# EVB-NORA-B2_SCHEM_0004_Connectors_Memory.net
KiCad netlist of a schematic drawn in Altium Designer
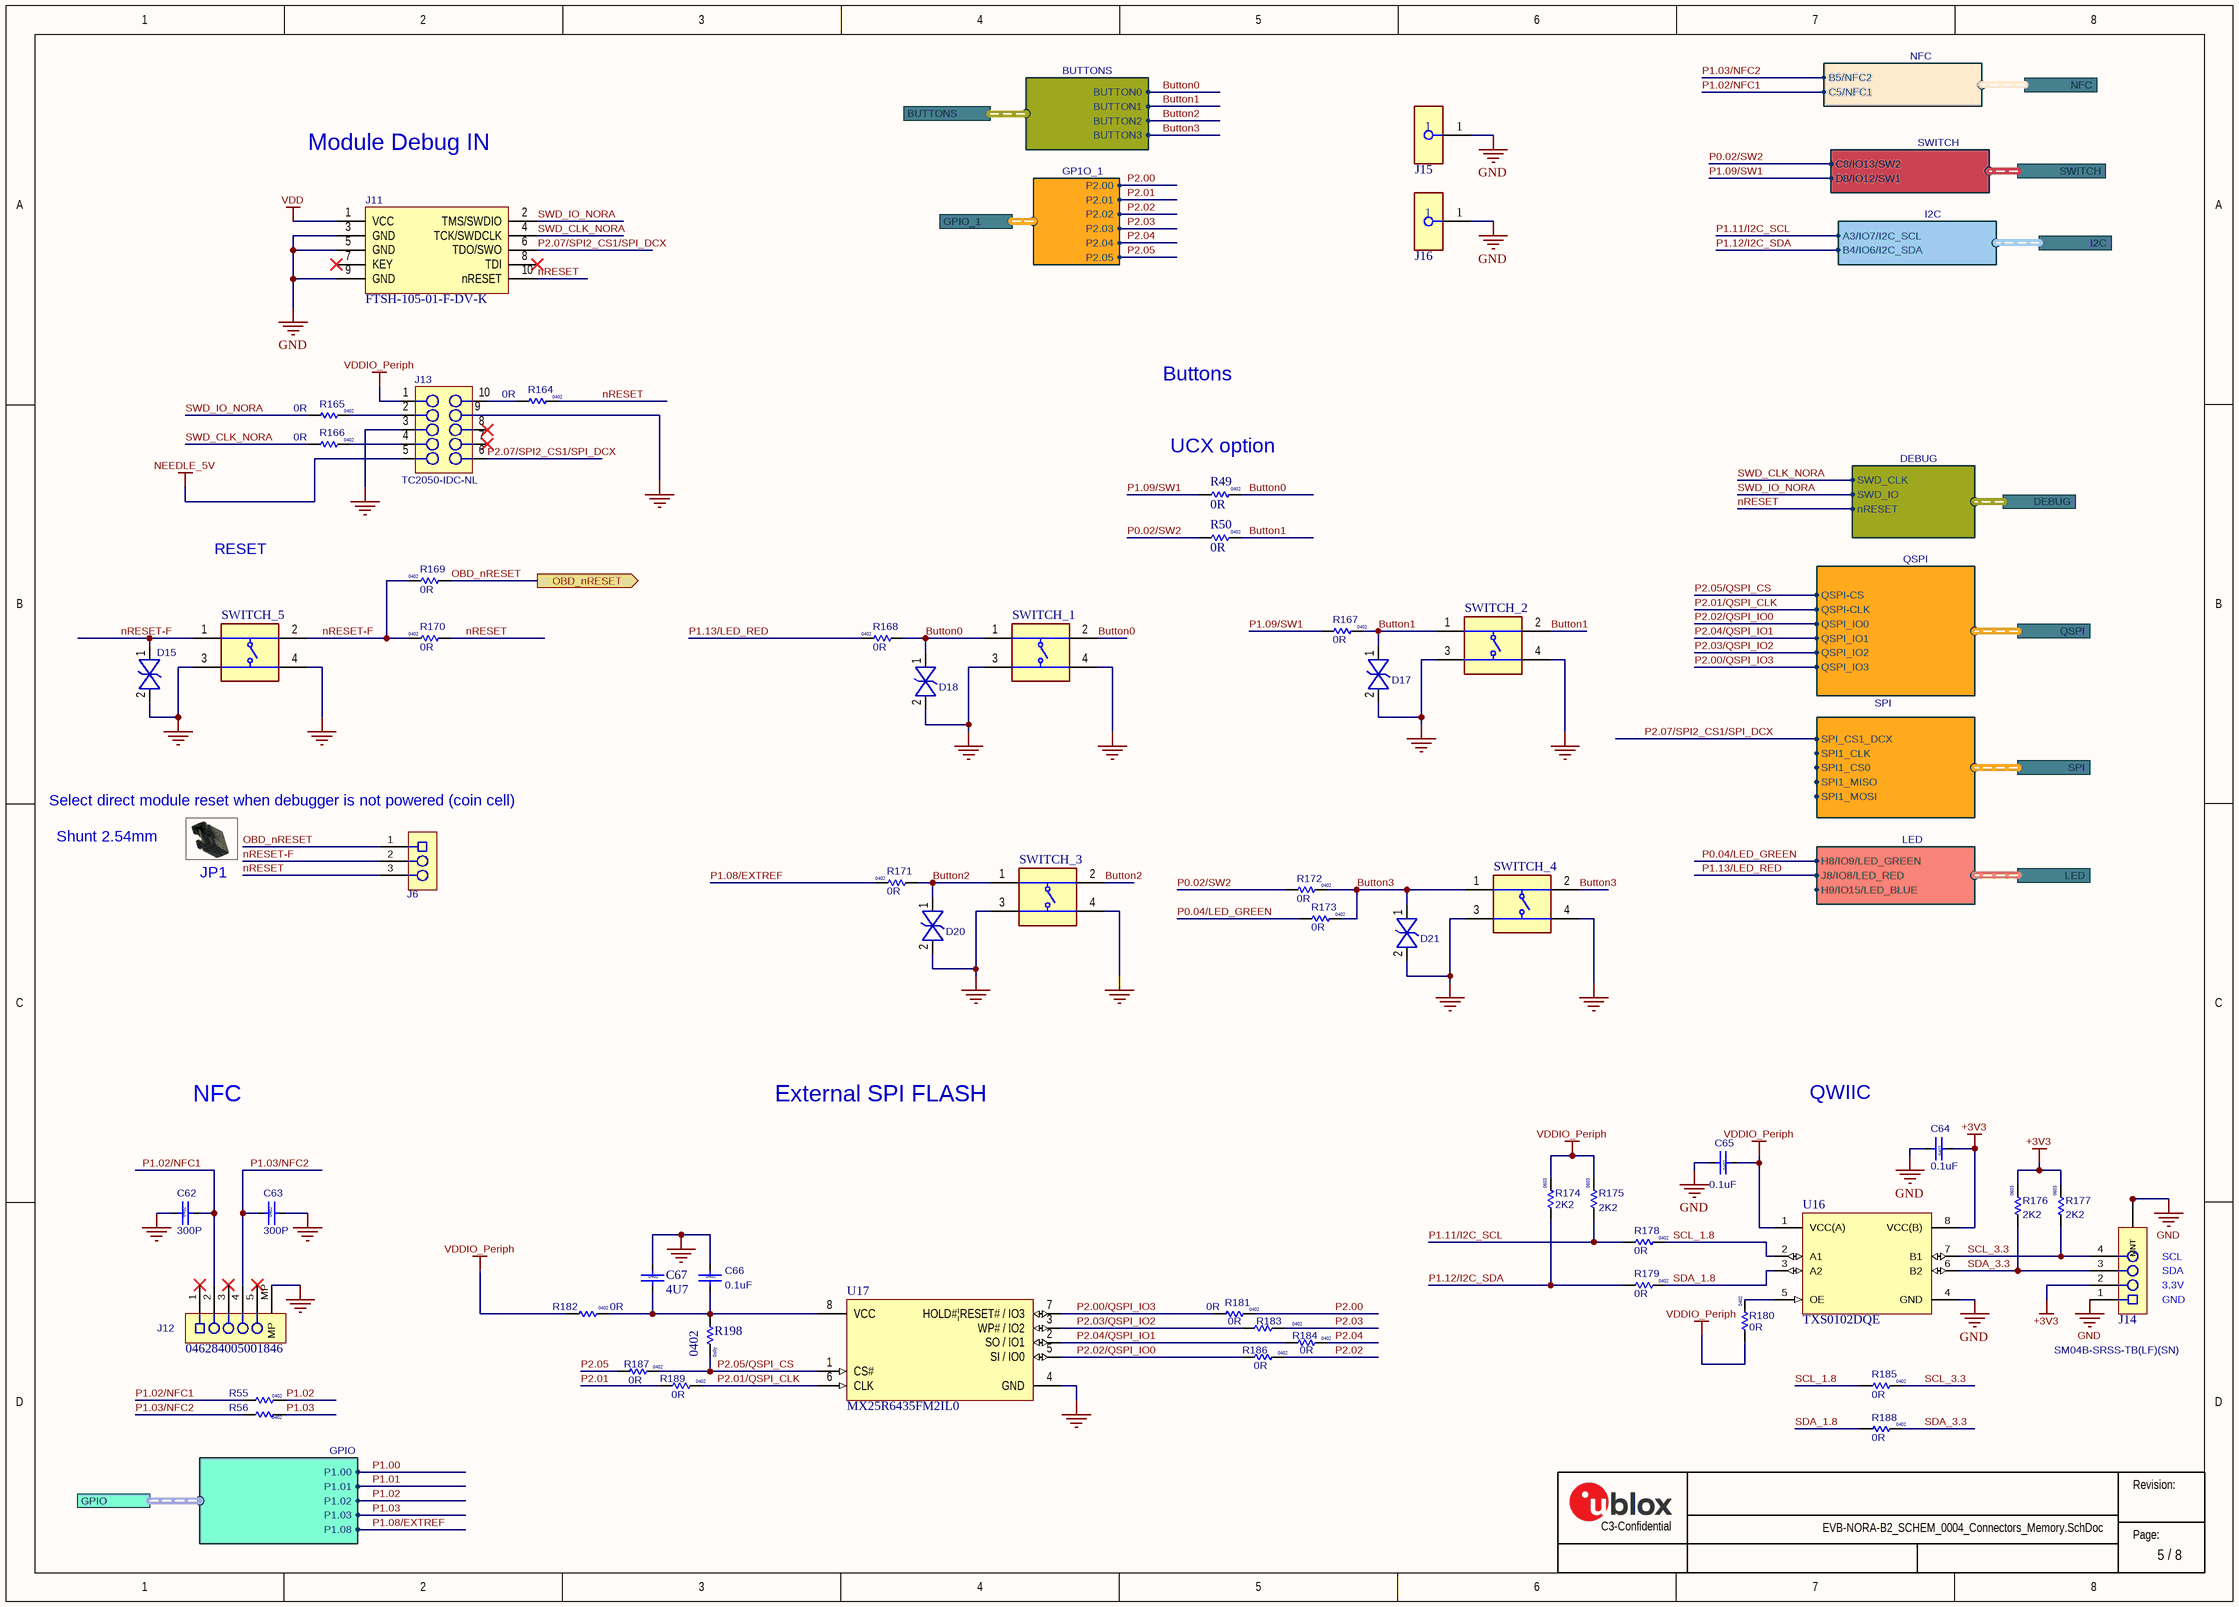
[diagram p0: EVB-NORA-B2_SCHEM_0004_Connectors_Memory.SchDoc]

(export (version "E")
  (design (tool "Eeschema 10.0.6"))
  (components
    (comp (ref "C62")
      (value "300P")
      (footprint "Cap 0402 HD")
      (description "CAP CER C0G 0402 300P 50V")
      (fields
        (field (name "SIZE") "0402")
        (field (name "PART NUMBER") "UBXH01-0000594")
        (field (name "MANUFACTURER") "Murata Manufacturing Company, Ltd.")
        (field (name "EDITOR") "eric.moog")
      )
      (libsource (lib "UBX_Parts_DB_Lib") (part "Cap Chip"))
    )
    (comp (ref "C63")
      (value "300P")
      (footprint "Cap 0402 HD")
      (description "CAP CER C0G 0402 300P 50V")
      (fields
        (field (name "SIZE") "0402")
        (field (name "PART NUMBER") "UBXH01-0000594")
        (field (name "MANUFACTURER") "Murata Manufacturing Company, Ltd.")
        (field (name "EDITOR") "eric.moog")
      )
      (libsource (lib "UBX_Parts_DB_Lib") (part "Cap Chip"))
    )
    (comp (ref "C64")
      (value "0.1uF")
      (footprint "Cap 0402 HD")
      (description "Cap, Ceramic 0.1uF 10V 10% X5R 0402")
      (fields
        (field (name "SIZE") "0402")
        (field (name "PART NUMBER") "120-00016")
        (field (name "MANUFACTURER") "Murata Electronics North America")
      )
      (libsource (lib "Arena_Parts_DB_Lib") (part "Cap Chip"))
    )
    (comp (ref "C65")
      (value "0.1uF")
      (footprint "Cap 0402 HD")
      (description "Cap, Ceramic 0.1uF 10V 10% X5R 0402")
      (fields
        (field (name "SIZE") "0402")
        (field (name "PART NUMBER") "120-00016")
        (field (name "MANUFACTURER") "Murata Electronics North America")
      )
      (libsource (lib "Arena_Parts_DB_Lib") (part "Cap Chip"))
    )
    (comp (ref "C66")
      (value "0.1uF")
      (footprint "Cap 0402 HD")
      (description "Cap, Ceramic 0.1uF 10V 10% X5R 0402")
      (fields
        (field (name "SIZE") "0402")
        (field (name "PART NUMBER") "120-00016")
        (field (name "MANUFACTURER") "Murata Electronics North America")
      )
      (libsource (lib "Arena_Parts_DB_Lib") (part "Cap Chip"))
    )
    (comp (ref "C67")
      (value "4U7")
      (footprint "Cap 0402 HD")
      (description "CAP CER X5R 0402 4U7 20% 10V")
      (fields
        (field (name "SIZE") "0402")
        (field (name "PART NUMBER") "UBXH01-0000243")
        (field (name "TOLERANCE") "20%")
        (field (name "EDITOR") "martin.pilik")
        (field (name "RELEASED BY") "fabrice.bret-dibat")
      )
      (libsource (lib "UBX_Parts_DB_Lib") (part "Cap Chip"))
    )
    (comp (ref "D15")
      (value "110-00019")
      (footprint "SOD-923")
      (description "ESD9B3.3ST5G")
      (fields (field (name "MANUFACTURER") "ON Semiconductor") (field (name "VOLTAGE") "3.3V"))
      (libsource (lib "Arena_Parts_DB_Lib") (part "Diode_TVS"))
    )
    (comp (ref "D17")
      (value "110-00019")
      (footprint "SOD-923")
      (description "ESD9B3.3ST5G")
      (fields (field (name "MANUFACTURER") "ON Semiconductor") (field (name "VOLTAGE") "3.3V"))
      (libsource (lib "Arena_Parts_DB_Lib") (part "Diode_TVS"))
    )
    (comp (ref "D18")
      (value "110-00019")
      (footprint "SOD-923")
      (description "ESD9B3.3ST5G")
      (fields (field (name "MANUFACTURER") "ON Semiconductor") (field (name "VOLTAGE") "3.3V"))
      (libsource (lib "Arena_Parts_DB_Lib") (part "Diode_TVS"))
    )
    (comp (ref "D20")
      (value "110-00019")
      (footprint "SOD-923")
      (description "ESD9B3.3ST5G")
      (fields (field (name "MANUFACTURER") "ON Semiconductor") (field (name "VOLTAGE") "3.3V"))
      (libsource (lib "Arena_Parts_DB_Lib") (part "Diode_TVS"))
    )
    (comp (ref "D21")
      (value "110-00019")
      (footprint "SOD-923")
      (description "ESD9B3.3ST5G")
      (fields (field (name "MANUFACTURER") "ON Semiconductor") (field (name "VOLTAGE") "3.3V"))
      (libsource (lib "Arena_Parts_DB_Lib") (part "Diode_TVS"))
    )
    (comp (ref "J6")
      (value "UBXH04-0000792")
      (footprint "HDR-0.1P-3Pin-1Row-SMT")
      (description "1-ROW SMD CONN 100MIL GRID 3 -PIN 100V 3A")
      (fields (field (name "MANUFACTURER") "HARWiN") (field (name "EDITOR") "eric.moog"))
      (libsource (lib "UBX_Parts_DB_Lib") (part "CON-3Pin_1Row"))
    )
    (comp (ref "J11")
      (value "130-00099")
      (footprint "HDR.050P-10Pin-2x5-SMT_Key")
      (description "Header 0.05\" 10Pin 2Row SMD Black")
      (fields (field (name "MANUFACTURER") "Samtec") (field (name "MANUFACTURER P/N") "FTSH-105-01-F-DV-K"))
      (libsource (lib "Arena_Parts_DB_Lib") (part "JTAG-10Pin"))
    )
    (comp (ref "J12")
      (value "UBXH04-0000798")
      (footprint "AVX/Kyocera - 046284005001846")
      (description "0.50MM PITCH SMD RA FFC FPC CONN 5 -PIN 50V 400mA")
      (fields
        (field (name "MANUFACTURER P/N") "046284005001846")
        (field (name "VOLTAGE") "50V")
        (field (name "MANUFACTURER") "AVX")
        (field (name "EDITOR") "eric.moog")
      )
      (libsource (lib "UBX_Parts_DB_Lib") (part "CON-5Pin_1Row-046284005001846"))
    )
    (comp (ref "J13")
      (value "TC2050-IDC-NL")
      (footprint "TC2050-IDC-NL")
      (description "CON PADS FOR CBL PLUG-OF-NAILS 10-PIN NO LEGS")
      (fields
        (field (name "MANUFACTURER P/N") "TC2050-IDC-NL")
        (field (name "MANUFACTURER") "TAG Connect")
        (field (name "ADDED BY") "Paul B")
      )
      (libsource (lib "LEGACY_Rigado_AltiumLib") (part "CON-10Pin_2Row_ALT"))
    )
    (comp (ref "J14")
      (value "UBXH04-0000797")
      (footprint "SM04B-SRSS-TB")
      (description "CONN JST SH SERIES SMT 4 POS MALE 1MM RA 50V 1A")
      (fields
        (field (name "MANUFACTURER PART NUMBER 1") "SM04B-SRSS-TB(LF)(SN)")
        (field (name "VOLTAGE") "None")
        (field (name "MANUFACTURER") "JST")
        (field (name "EDITOR") "eric.moog")
      )
      (libsource (lib "UBX_Parts_DB_Lib") (part "SM04B-SRSS-TB"))
    )
    (comp (ref "J15")
      (value "~")
      (footprint "Harwin_0_MFG")
      (libsource (lib "Conn_Harwin_S1751-46R_eec") (part "S1751-46R"))
    )
    (comp (ref "J16")
      (value "~")
      (footprint "Harwin_0_MFG")
      (libsource (lib "Conn_Harwin_S1751-46R_eec") (part "S1751-46R"))
    )
    (comp (ref "R49")
      (value "0R")
      (footprint "RES_0402_1100Lx600Wx400H_500x600Pad_400G_FLX")
      (description "RES THICK FILM CHIP 0402 0R 0 100mW")
      (fields
        (field (name "SIZE") "0402")
        (field (name "PART NUMBER") "UBXH18-0003002")
        (field (name "TOLERANCE") "0")
        (field (name "EDITOR") "charlotte.biber")
        (field (name "RELEASED BY") "peter.mueller")
      )
      (libsource (lib "UBX_Parts_DB_Lib") (part "Res sm"))
    )
    (comp (ref "R50")
      (value "0R")
      (footprint "RES_0402_1100Lx600Wx400H_500x600Pad_400G_FLX")
      (description "RES THICK FILM CHIP 0402 0R 0 100mW")
      (fields
        (field (name "SIZE") "0402")
        (field (name "PART NUMBER") "UBXH18-0003002")
        (field (name "TOLERANCE") "0")
        (field (name "EDITOR") "charlotte.biber")
        (field (name "RELEASED BY") "peter.mueller")
      )
      (libsource (lib "UBX_Parts_DB_Lib") (part "Res sm"))
    )
    (comp (ref "R55")
      (value "UBXH18-0003002")
      (footprint "RES 0402 HD")
      (description "RES THICK FILM CHIP 0402 0R 0 100mW")
      (fields
        (field (name "SIZE") "0402")
        (field (name "TOLERANCE") "0")
        (field (name "MANUFACTURER") "KOA")
        (field (name "EDITOR") "charlotte.biber")
        (field (name "RELEASED BY") "peter.mueller")
      )
      (libsource (lib "UBX_Parts_DB_Lib") (part "Res sm"))
    )
    (comp (ref "R56")
      (value "UBXH18-0003002")
      (footprint "RES 0402 HD")
      (description "RES THICK FILM CHIP 0402 0R 0 100mW")
      (fields
        (field (name "SIZE") "0402")
        (field (name "TOLERANCE") "0")
        (field (name "MANUFACTURER") "KOA")
        (field (name "EDITOR") "charlotte.biber")
        (field (name "RELEASED BY") "peter.mueller")
      )
      (libsource (lib "UBX_Parts_DB_Lib") (part "Res sm"))
    )
    (comp (ref "R164")
      (value "0R")
      (footprint "RES 0402 HD")
      (description "RES THICK FILM CHIP 0402 0R 0 100mW")
      (fields
        (field (name "SIZE") "0402")
        (field (name "PART NUMBER") "UBXH18-0003002")
        (field (name "TOLERANCE") "0")
        (field (name "EDITOR") "charlotte.biber")
        (field (name "RELEASED BY") "peter.mueller")
      )
      (libsource (lib "UBX_Parts_DB_Lib") (part "Res sm"))
    )
    (comp (ref "R165")
      (value "0R")
      (footprint "RES 0402 HD")
      (description "RES THICK FILM CHIP 0402 0R 0 100mW")
      (fields
        (field (name "SIZE") "0402")
        (field (name "PART NUMBER") "UBXH18-0003002")
        (field (name "TOLERANCE") "0")
        (field (name "EDITOR") "charlotte.biber")
        (field (name "RELEASED BY") "peter.mueller")
      )
      (libsource (lib "UBX_Parts_DB_Lib") (part "Res sm"))
    )
    (comp (ref "R166")
      (value "0R")
      (footprint "RES 0402 HD")
      (description "RES THICK FILM CHIP 0402 0R 0 100mW")
      (fields
        (field (name "SIZE") "0402")
        (field (name "PART NUMBER") "UBXH18-0003002")
        (field (name "TOLERANCE") "0")
        (field (name "EDITOR") "charlotte.biber")
        (field (name "RELEASED BY") "peter.mueller")
      )
      (libsource (lib "UBX_Parts_DB_Lib") (part "Res sm"))
    )
    (comp (ref "R167")
      (value "0R")
      (footprint "RES 0402 HD")
      (description "RES THICK FILM CHIP 0402 0R 0 100mW")
      (fields
        (field (name "SIZE") "0402")
        (field (name "PART NUMBER") "UBXH18-0003002")
        (field (name "TOLERANCE") "0")
        (field (name "EDITOR") "charlotte.biber")
        (field (name "RELEASED BY") "peter.mueller")
      )
      (libsource (lib "UBX_Parts_DB_Lib") (part "Res sm"))
    )
    (comp (ref "R168")
      (value "0R")
      (footprint "RES 0402 HD")
      (description "RES THICK FILM CHIP 0402 0R 0 100mW")
      (fields
        (field (name "SIZE") "0402")
        (field (name "PART NUMBER") "UBXH18-0003002")
        (field (name "TOLERANCE") "0")
        (field (name "EDITOR") "charlotte.biber")
        (field (name "RELEASED BY") "peter.mueller")
      )
      (libsource (lib "UBX_Parts_DB_Lib") (part "Res sm"))
    )
    (comp (ref "R169")
      (value "0R")
      (footprint "RES 0402 HD")
      (description "RES THICK FILM CHIP 0402 0R 0 100mW")
      (fields
        (field (name "SIZE") "0402")
        (field (name "PART NUMBER") "UBXH18-0003002")
        (field (name "TOLERANCE") "0")
        (field (name "EDITOR") "charlotte.biber")
        (field (name "RELEASED BY") "peter.mueller")
      )
      (libsource (lib "UBX_Parts_DB_Lib") (part "Res sm"))
    )
    (comp (ref "R170")
      (value "0R")
      (footprint "RES 0402 HD")
      (description "RES THICK FILM CHIP 0402 0R 0 100mW")
      (fields
        (field (name "SIZE") "0402")
        (field (name "PART NUMBER") "UBXH18-0003002")
        (field (name "TOLERANCE") "0")
        (field (name "EDITOR") "charlotte.biber")
        (field (name "RELEASED BY") "peter.mueller")
      )
      (libsource (lib "UBX_Parts_DB_Lib") (part "Res sm"))
    )
    (comp (ref "R171")
      (value "0R")
      (footprint "RES 0402 HD")
      (description "RES THICK FILM CHIP 0402 0R 0 100mW")
      (fields
        (field (name "SIZE") "0402")
        (field (name "PART NUMBER") "UBXH18-0003002")
        (field (name "TOLERANCE") "0")
        (field (name "EDITOR") "charlotte.biber")
        (field (name "RELEASED BY") "peter.mueller")
      )
      (libsource (lib "UBX_Parts_DB_Lib") (part "Res sm"))
    )
    (comp (ref "R172")
      (value "0R")
      (footprint "RES 0402 HD")
      (description "RES THICK FILM CHIP 0402 0R 0 100mW")
      (fields
        (field (name "SIZE") "0402")
        (field (name "PART NUMBER") "UBXH18-0003002")
        (field (name "TOLERANCE") "0")
        (field (name "EDITOR") "charlotte.biber")
        (field (name "RELEASED BY") "peter.mueller")
      )
      (libsource (lib "UBX_Parts_DB_Lib") (part "Res sm"))
    )
    (comp (ref "R173")
      (value "0R")
      (footprint "RES 0402 HD")
      (description "RES THICK FILM CHIP 0402 0R 0 100mW")
      (fields
        (field (name "SIZE") "0402")
        (field (name "PART NUMBER") "UBXH18-0003002")
        (field (name "TOLERANCE") "0")
        (field (name "EDITOR") "charlotte.biber")
        (field (name "RELEASED BY") "peter.mueller")
      )
      (libsource (lib "UBX_Parts_DB_Lib") (part "Res sm"))
    )
    (comp (ref "R174")
      (value "2K2")
      (footprint "RES_0603_1700Lx950Wx600H_600x1000Pad_800G_FLX")
      (description "RES THICK FILM CHIP 0603 2K2 5% 100mW")
      (fields
        (field (name "SIZE") "0603")
        (field (name "PART NUMBER") "UBXH18-0007081")
        (field (name "TOLERANCE") "5%")
        (field (name "EDITOR") "roland.rust")
        (field (name "RELEASED BY") "roland.rust")
      )
      (libsource (lib "UBX_Parts_DB_Lib") (part "Res sm"))
    )
    (comp (ref "R175")
      (value "2K2")
      (footprint "RES_0603_1700Lx950Wx600H_600x1000Pad_800G_FLX")
      (description "RES THICK FILM CHIP 0603 2K2 5% 100mW")
      (fields
        (field (name "SIZE") "0603")
        (field (name "PART NUMBER") "UBXH18-0007081")
        (field (name "TOLERANCE") "5%")
        (field (name "EDITOR") "roland.rust")
        (field (name "RELEASED BY") "roland.rust")
      )
      (libsource (lib "UBX_Parts_DB_Lib") (part "Res sm"))
    )
    (comp (ref "R176")
      (value "2K2")
      (footprint "RES_0603_1700Lx950Wx600H_600x1000Pad_800G_FLX")
      (description "RES THICK FILM CHIP 0603 2K2 5% 100mW")
      (fields
        (field (name "SIZE") "0603")
        (field (name "PART NUMBER") "UBXH18-0007081")
        (field (name "TOLERANCE") "5%")
        (field (name "EDITOR") "roland.rust")
        (field (name "RELEASED BY") "roland.rust")
      )
      (libsource (lib "UBX_Parts_DB_Lib") (part "Res sm"))
    )
    (comp (ref "R177")
      (value "2K2")
      (footprint "RES_0603_1700Lx950Wx600H_600x1000Pad_800G_FLX")
      (description "RES THICK FILM CHIP 0603 2K2 5% 100mW")
      (fields
        (field (name "SIZE") "0603")
        (field (name "PART NUMBER") "UBXH18-0007081")
        (field (name "TOLERANCE") "5%")
        (field (name "EDITOR") "roland.rust")
        (field (name "RELEASED BY") "roland.rust")
      )
      (libsource (lib "UBX_Parts_DB_Lib") (part "Res sm"))
    )
    (comp (ref "R178")
      (value "0R")
      (footprint "RES 0402 HD")
      (description "RES THICK FILM CHIP 0402 0R 0 100mW")
      (fields
        (field (name "SIZE") "0402")
        (field (name "PART NUMBER") "UBXH18-0003002")
        (field (name "TOLERANCE") "0")
        (field (name "EDITOR") "charlotte.biber")
        (field (name "RELEASED BY") "peter.mueller")
      )
      (libsource (lib "UBX_Parts_DB_Lib") (part "Res sm"))
    )
    (comp (ref "R179")
      (value "0R")
      (footprint "RES 0402 HD")
      (description "RES THICK FILM CHIP 0402 0R 0 100mW")
      (fields
        (field (name "SIZE") "0402")
        (field (name "PART NUMBER") "UBXH18-0003002")
        (field (name "TOLERANCE") "0")
        (field (name "EDITOR") "charlotte.biber")
        (field (name "RELEASED BY") "peter.mueller")
      )
      (libsource (lib "UBX_Parts_DB_Lib") (part "Res sm"))
    )
    (comp (ref "R180")
      (value "0R")
      (footprint "RES 0402 HD")
      (description "RES THICK FILM CHIP 0402 0R 0 100mW")
      (fields
        (field (name "SIZE") "0402")
        (field (name "PART NUMBER") "UBXH18-0003002")
        (field (name "TOLERANCE") "0")
        (field (name "EDITOR") "charlotte.biber")
        (field (name "RELEASED BY") "peter.mueller")
      )
      (libsource (lib "UBX_Parts_DB_Lib") (part "Res sm"))
    )
    (comp (ref "R181")
      (value "0R")
      (footprint "RES 0402 HD")
      (description "RES THICK FILM CHIP 0402 0R 0 100mW")
      (fields
        (field (name "SIZE") "0402")
        (field (name "PART NUMBER") "UBXH18-0003002")
        (field (name "TOLERANCE") "0")
        (field (name "EDITOR") "charlotte.biber")
        (field (name "RELEASED BY") "peter.mueller")
      )
      (libsource (lib "UBX_Parts_DB_Lib") (part "Res sm"))
    )
    (comp (ref "R182")
      (value "0R")
      (footprint "RES 0402 HD")
      (description "RES THICK FILM CHIP 0402 0R 0 100mW")
      (fields
        (field (name "SIZE") "0402")
        (field (name "PART NUMBER") "UBXH18-0003002")
        (field (name "TOLERANCE") "0")
        (field (name "EDITOR") "charlotte.biber")
        (field (name "RELEASED BY") "peter.mueller")
      )
      (libsource (lib "UBX_Parts_DB_Lib") (part "Res sm"))
    )
    (comp (ref "R183")
      (value "0R")
      (footprint "RES 0402 HD")
      (description "RES THICK FILM CHIP 0402 0R 0 100mW")
      (fields
        (field (name "SIZE") "0402")
        (field (name "PART NUMBER") "UBXH18-0003002")
        (field (name "TOLERANCE") "0")
        (field (name "EDITOR") "charlotte.biber")
        (field (name "RELEASED BY") "peter.mueller")
      )
      (libsource (lib "UBX_Parts_DB_Lib") (part "Res sm"))
    )
    (comp (ref "R184")
      (value "0R")
      (footprint "RES 0402 HD")
      (description "RES THICK FILM CHIP 0402 0R 0 100mW")
      (fields
        (field (name "SIZE") "0402")
        (field (name "PART NUMBER") "UBXH18-0003002")
        (field (name "TOLERANCE") "0")
        (field (name "EDITOR") "charlotte.biber")
        (field (name "RELEASED BY") "peter.mueller")
      )
      (libsource (lib "UBX_Parts_DB_Lib") (part "Res sm"))
    )
    (comp (ref "R185")
      (value "0R")
      (footprint "RES 0402 HD")
      (description "RES THICK FILM CHIP 0402 0R 0 100mW")
      (fields
        (field (name "SIZE") "0402")
        (field (name "PART NUMBER") "UBXH18-0003002")
        (field (name "TOLERANCE") "0")
        (field (name "EDITOR") "charlotte.biber")
        (field (name "RELEASED BY") "peter.mueller")
      )
      (libsource (lib "UBX_Parts_DB_Lib") (part "Res sm"))
    )
    (comp (ref "R186")
      (value "0R")
      (footprint "RES 0402 HD")
      (description "RES THICK FILM CHIP 0402 0R 0 100mW")
      (fields
        (field (name "SIZE") "0402")
        (field (name "PART NUMBER") "UBXH18-0003002")
        (field (name "TOLERANCE") "0")
        (field (name "EDITOR") "charlotte.biber")
        (field (name "RELEASED BY") "peter.mueller")
      )
      (libsource (lib "UBX_Parts_DB_Lib") (part "Res sm"))
    )
    (comp (ref "R187")
      (value "0R")
      (footprint "RES 0402 HD")
      (description "RES THICK FILM CHIP 0402 0R 0 100mW")
      (fields
        (field (name "SIZE") "0402")
        (field (name "PART NUMBER") "UBXH18-0003002")
        (field (name "TOLERANCE") "0")
        (field (name "EDITOR") "charlotte.biber")
        (field (name "RELEASED BY") "peter.mueller")
      )
      (libsource (lib "UBX_Parts_DB_Lib") (part "Res sm"))
    )
    (comp (ref "R188")
      (value "0R")
      (footprint "RES 0402 HD")
      (description "RES THICK FILM CHIP 0402 0R 0 100mW")
      (fields
        (field (name "SIZE") "0402")
        (field (name "PART NUMBER") "UBXH18-0003002")
        (field (name "TOLERANCE") "0")
        (field (name "EDITOR") "charlotte.biber")
        (field (name "RELEASED BY") "peter.mueller")
      )
      (libsource (lib "UBX_Parts_DB_Lib") (part "Res sm"))
    )
    (comp (ref "R189")
      (value "0R")
      (footprint "RES 0402 HD")
      (description "RES THICK FILM CHIP 0402 0R 0 100mW")
      (fields
        (field (name "SIZE") "0402")
        (field (name "PART NUMBER") "UBXH18-0003002")
        (field (name "TOLERANCE") "0")
        (field (name "EDITOR") "charlotte.biber")
        (field (name "RELEASED BY") "peter.mueller")
      )
      (libsource (lib "UBX_Parts_DB_Lib") (part "Res sm"))
    )
    (comp (ref "R198")
      (value "UBXH18-0000005")
      (footprint "RES 0402 HD")
      (description "RES THICK FILM CHIP 0402 100K 1% 63mW")
      (fields
        (field (name "SIZE") "0402")
        (field (name "TOLERANCE") "1%")
        (field (name "MANUFACTURER") "KOA")
        (field (name "CASE/PACKAGE") "0x0y")
        (field (name "EDITOR") "dario.antonaz")
        (field (name "RELEASED BY") "sandro.sestan")
      )
      (libsource (lib "UBX_Parts_DB_Lib") (part "Res sm"))
    )
    (comp (ref "SWITCH_1")
      (value "~")
      (footprint "PTS810SJG250SMTRLFS")
      (description "Switch")
      (fields
        (field (name "MANUFACTURER_PART_NUMBER") "PTS810SJK250SMTRLFS")
        (field (name "MOUSER PART NUMBER") "611-PTS810SJK250SMTR")
      )
      (libsource (lib "SamacSys") (part "PTS810SJK250SMTRLFS"))
    )
    (comp (ref "SWITCH_2")
      (value "~")
      (footprint "PTS810SJG250SMTRLFS")
      (description "Switch")
      (fields
        (field (name "MANUFACTURER_PART_NUMBER") "PTS810SJK250SMTRLFS")
        (field (name "MOUSER PART NUMBER") "611-PTS810SJK250SMTR")
      )
      (libsource (lib "SamacSys") (part "PTS810SJK250SMTRLFS"))
    )
    (comp (ref "SWITCH_3")
      (value "~")
      (footprint "PTS810SJG250SMTRLFS")
      (description "Switch")
      (fields
        (field (name "MANUFACTURER_PART_NUMBER") "PTS810SJK250SMTRLFS")
        (field (name "MOUSER PART NUMBER") "611-PTS810SJK250SMTR")
      )
      (libsource (lib "SamacSys") (part "PTS810SJK250SMTRLFS"))
    )
    (comp (ref "SWITCH_4")
      (value "~")
      (footprint "PTS810SJG250SMTRLFS")
      (description "Switch")
      (fields
        (field (name "MANUFACTURER_PART_NUMBER") "PTS810SJK250SMTRLFS")
        (field (name "MOUSER PART NUMBER") "611-PTS810SJK250SMTR")
      )
      (libsource (lib "SamacSys") (part "PTS810SJK250SMTRLFS"))
    )
    (comp (ref "SWITCH_5")
      (value "~")
      (footprint "PTS810SJG250SMTRLFS")
      (description "Switch")
      (fields
        (field (name "MANUFACTURER_PART_NUMBER") "PTS810SJK250SMTRLFS")
        (field (name "MOUSER PART NUMBER") "611-PTS810SJK250SMTR")
      )
      (libsource (lib "SamacSys") (part "PTS810SJK250SMTRLFS"))
    )
    (comp (ref "U16")
      (value "TXS0102DQE")
      (footprint "DQE0008A")
      (description "TXS0102 2-BIT BIDIRECTIONAL VOLTAGE-LEVEL TRANSLATOR X2SON-8 TXS0102DQE 5.5V")
      (fields
        (field (name "PART NUMBER") "UBXH10-0000108")
        (field (name "MANUFACTURER") "Texas Instruments")
        (field (name "EDITOR") "eric.moog")
      )
      (libsource (lib "UBX_Parts_DB_Lib") (part "TXS0102DQE"))
    )
    (comp (ref "U17")
      (value "UBXH13-0000149")
      (footprint "SOIC-8")
      (description "MACRONIX MX25R6435FM2IL0 64MBIT SERIAL QUAD I/O SPI FLASH MEMORY 1.65 - 3.6V 8-SOP (200mil)")
      (fields (field (name "MANUFACTURER P/N") "MX25R6435FM2IL0") (field (name "OWNER") "Hozaifa Abdelgadir"))
      (libsource (lib "UBX_Arena") (part "SPI_Flash_Memory_8Pin"))
    )
  )
  (nets
    (net (code "11") (name "+3V3") (class "Default")
      (node (ref "C64") (pin "1") (pinfunction "1_1") (pintype "passive"))
      (node (ref "J14") (pin "2") (pinfunction "2_2") (pintype "passive"))
      (node (ref "R176") (pin "2") (pinfunction "2_2") (pintype "passive"))
      (node (ref "R177") (pin "2") (pinfunction "2_2") (pintype "passive"))
      (node (ref "U16") (pin "8") (pinfunction "VCC(B)_8") (pintype "power_in"))
    )
    (net (code "12") (name "/Button0") (class "Default")
      (node (ref "D18") (pin "1") (pintype "passive"))
      (node (ref "R168") (pin "1") (pinfunction "1_1") (pintype "passive"))
      (node (ref "R49") (pin "2") (pinfunction "2_2") (pintype "passive"))
      (node (ref "SWITCH_1") (pin "1") (pinfunction "1_1") (pintype "passive"))
      (node (ref "SWITCH_1") (pin "2") (pinfunction "2_2") (pintype "passive"))
    )
    (net (code "13") (name "/Button1") (class "Default")
      (node (ref "D17") (pin "1") (pintype "passive"))
      (node (ref "R167") (pin "1") (pinfunction "1_1") (pintype "passive"))
      (node (ref "R50") (pin "2") (pinfunction "2_2") (pintype "passive"))
      (node (ref "SWITCH_2") (pin "1") (pinfunction "1_1") (pintype "passive"))
      (node (ref "SWITCH_2") (pin "2") (pinfunction "2_2") (pintype "passive"))
    )
    (net (code "14") (name "/Button2") (class "Default")
      (node (ref "D20") (pin "1") (pintype "passive"))
      (node (ref "R171") (pin "1") (pinfunction "1_1") (pintype "passive"))
      (node (ref "SWITCH_3") (pin "1") (pinfunction "1_1") (pintype "passive"))
      (node (ref "SWITCH_3") (pin "2") (pinfunction "2_2") (pintype "passive"))
    )
    (net (code "15") (name "/Button3") (class "Default")
      (node (ref "D21") (pin "1") (pintype "passive"))
      (node (ref "R172") (pin "1") (pinfunction "1_1") (pintype "passive"))
      (node (ref "R173") (pin "1") (pinfunction "1_1") (pintype "passive"))
      (node (ref "SWITCH_4") (pin "1") (pinfunction "1_1") (pintype "passive"))
      (node (ref "SWITCH_4") (pin "2") (pinfunction "2_2") (pintype "passive"))
    )
    (net (code "16") (name "/OBD_nRESET") (class "Default")
      (node (ref "J6") (pin "1") (pinfunction "1_1") (pintype "passive"))
      (node (ref "R169") (pin "1") (pinfunction "1_1") (pintype "passive"))
    )
    (net (code "17") (name "/P0.02{slash}SW2") (class "Default")
      (node (ref "R172") (pin "2") (pinfunction "2_2") (pintype "passive"))
      (node (ref "R50") (pin "1") (pinfunction "1_1") (pintype "passive"))
    )
    (net (code "18") (name "/P0.04{slash}LED_GREEN") (class "Default")
      (node (ref "R173") (pin "2") (pinfunction "2_2") (pintype "passive"))
    )
    (net (code "21") (name "/P1.02") (class "Default")
      (node (ref "R55") (pin "1") (pinfunction "1_1") (pintype "passive"))
    )
    (net (code "22") (name "/P1.02{slash}NFC1") (class "Default")
      (node (ref "C62") (pin "2") (pinfunction "2_2") (pintype "passive"))
      (node (ref "J12") (pin "2") (pinfunction "2_2") (pintype "passive"))
      (node (ref "R55") (pin "2") (pinfunction "2_2") (pintype "passive"))
    )
    (net (code "23") (name "/P1.03") (class "Default")
      (node (ref "R56") (pin "1") (pinfunction "1_1") (pintype "passive"))
    )
    (net (code "24") (name "/P1.03{slash}NFC2") (class "Default")
      (node (ref "C63") (pin "1") (pinfunction "1_1") (pintype "passive"))
      (node (ref "J12") (pin "4") (pinfunction "4_4") (pintype "passive"))
      (node (ref "R56") (pin "2") (pinfunction "2_2") (pintype "passive"))
    )
    (net (code "25") (name "/P1.08{slash}EXTREF") (class "Default")
      (node (ref "R171") (pin "2") (pinfunction "2_2") (pintype "passive"))
    )
    (net (code "26") (name "/P1.09{slash}SW1") (class "Default")
      (node (ref "R167") (pin "2") (pinfunction "2_2") (pintype "passive"))
      (node (ref "R49") (pin "1") (pinfunction "1_1") (pintype "passive"))
    )
    (net (code "27") (name "/P1.11{slash}I2C_SCL") (class "Default")
      (node (ref "R175") (pin "1") (pinfunction "1_1") (pintype "passive"))
      (node (ref "R178") (pin "2") (pinfunction "2_2") (pintype "passive"))
    )
    (net (code "28") (name "/P1.12{slash}I2C_SDA") (class "Default")
      (node (ref "R174") (pin "1") (pinfunction "1_1") (pintype "passive"))
      (node (ref "R179") (pin "2") (pinfunction "2_2") (pintype "passive"))
    )
    (net (code "29") (name "/P1.13{slash}LED_RED") (class "Default")
      (node (ref "R168") (pin "2") (pinfunction "2_2") (pintype "passive"))
    )
    (net (code "30") (name "/P2.00") (class "Default")
      (node (ref "R181") (pin "1") (pinfunction "1_1") (pintype "passive"))
    )
    (net (code "31") (name "/P2.00{slash}QSPI_IO3") (class "Default")
      (node (ref "R181") (pin "2") (pinfunction "2_2") (pintype "passive"))
      (node (ref "U17") (pin "7") (pinfunction "HOLD#¦RESET#_/_IO3_7") (pintype "bidirectional"))
    )
    (net (code "32") (name "/P2.01") (class "Default")
      (node (ref "R189") (pin "2") (pinfunction "2_2") (pintype "passive"))
    )
    (net (code "33") (name "/P2.01{slash}QSPI_CLK") (class "Default")
      (node (ref "R189") (pin "1") (pinfunction "1_1") (pintype "passive"))
      (node (ref "U17") (pin "6") (pinfunction "CLK_6") (pintype "input"))
    )
    (net (code "34") (name "/P2.02") (class "Default")
      (node (ref "R186") (pin "1") (pinfunction "1_1") (pintype "passive"))
    )
    (net (code "35") (name "/P2.02{slash}QSPI_IO0") (class "Default")
      (node (ref "R186") (pin "2") (pinfunction "2_2") (pintype "passive"))
      (node (ref "U17") (pin "5") (pinfunction "SI_/_IO0_5") (pintype "bidirectional"))
    )
    (net (code "36") (name "/P2.03") (class "Default")
      (node (ref "R183") (pin "1") (pinfunction "1_1") (pintype "passive"))
    )
    (net (code "37") (name "/P2.03{slash}QSPI_IO2") (class "Default")
      (node (ref "R183") (pin "2") (pinfunction "2_2") (pintype "passive"))
      (node (ref "U17") (pin "3") (pinfunction "WP#_/_IO2_3") (pintype "bidirectional"))
    )
    (net (code "38") (name "/P2.04") (class "Default")
      (node (ref "R184") (pin "1") (pinfunction "1_1") (pintype "passive"))
    )
    (net (code "39") (name "/P2.04{slash}QSPI_IO1") (class "Default")
      (node (ref "R184") (pin "2") (pinfunction "2_2") (pintype "passive"))
      (node (ref "U17") (pin "2") (pinfunction "SO_/_IO1_2") (pintype "bidirectional"))
    )
    (net (code "40") (name "/P2.05") (class "Default")
      (node (ref "R187") (pin "2") (pinfunction "2_2") (pintype "passive"))
    )
    (net (code "41") (name "/P2.05{slash}QSPI_CS") (class "Default")
      (node (ref "R187") (pin "1") (pinfunction "1_1") (pintype "passive"))
      (node (ref "R198") (pin "2") (pinfunction "2_2") (pintype "passive"))
      (node (ref "U17") (pin "1") (pinfunction "CS#_1") (pintype "input"))
    )
    (net (code "42") (name "/P2.07{slash}SPI2_CS1{slash}SPI_DCX") (class "Default")
      (node (ref "J11") (pin "6") (pinfunction "TDO/SWO_6") (pintype "passive"))
      (node (ref "J13") (pin "6") (pintype "passive"))
    )
    (net (code "43") (name "/SCL_1.8") (class "Default")
      (node (ref "R178") (pin "1") (pinfunction "1_1") (pintype "passive"))
      (node (ref "R185") (pin "2") (pinfunction "2_2") (pintype "passive"))
      (node (ref "U16") (pin "2") (pinfunction "A1_2") (pintype "bidirectional"))
    )
    (net (code "44") (name "/SCL_3.3") (class "Default")
      (node (ref "J14") (pin "4") (pinfunction "4_4") (pintype "passive"))
      (node (ref "R177") (pin "1") (pinfunction "1_1") (pintype "passive"))
      (node (ref "R185") (pin "1") (pinfunction "1_1") (pintype "passive"))
      (node (ref "U16") (pin "7") (pinfunction "B1_7") (pintype "bidirectional"))
    )
    (net (code "45") (name "/SDA_1.8") (class "Default")
      (node (ref "R179") (pin "1") (pinfunction "1_1") (pintype "passive"))
      (node (ref "R188") (pin "2") (pinfunction "2_2") (pintype "passive"))
      (node (ref "U16") (pin "3") (pinfunction "A2_3") (pintype "bidirectional"))
    )
    (net (code "46") (name "/SDA_3.3") (class "Default")
      (node (ref "J14") (pin "3") (pinfunction "3_3") (pintype "passive"))
      (node (ref "R176") (pin "1") (pinfunction "1_1") (pintype "passive"))
      (node (ref "R188") (pin "1") (pinfunction "1_1") (pintype "passive"))
      (node (ref "U16") (pin "6") (pinfunction "B2_6") (pintype "bidirectional"))
    )
    (net (code "47") (name "/SWD_CLK_NORA") (class "Default")
      (node (ref "J11") (pin "4") (pinfunction "TCK/SWDCLK_4") (pintype "passive"))
      (node (ref "R166") (pin "2") (pinfunction "2_2") (pintype "passive"))
    )
    (net (code "48") (name "/SWD_IO_NORA") (class "Default")
      (node (ref "J11") (pin "2") (pinfunction "TMS/SWDIO_2") (pintype "passive"))
      (node (ref "R165") (pin "2") (pinfunction "2_2") (pintype "passive"))
    )
    (net (code "49") (name "/nRESET") (class "Default")
      (node (ref "J11") (pin "10") (pinfunction "nRESET_10") (pintype "passive"))
      (node (ref "J6") (pin "3") (pinfunction "3_3") (pintype "passive"))
      (node (ref "R164") (pin "1") (pinfunction "1_1") (pintype "passive"))
      (node (ref "R170") (pin "1") (pinfunction "1_1") (pintype "passive"))
    )
    (net (code "50") (name "/nRESET-F") (class "Default")
      (node (ref "D15") (pin "1") (pintype "passive"))
      (node (ref "J6") (pin "2") (pinfunction "2_2") (pintype "passive"))
      (node (ref "R169") (pin "2") (pinfunction "2_2") (pintype "passive"))
      (node (ref "R170") (pin "2") (pinfunction "2_2") (pintype "passive"))
      (node (ref "SWITCH_5") (pin "1") (pinfunction "1_1") (pintype "passive"))
      (node (ref "SWITCH_5") (pin "2") (pinfunction "2_2") (pintype "passive"))
    )
    (net (code "61") (name "GND") (class "Default")
      (node (ref "C62") (pin "1") (pinfunction "1_1") (pintype "passive"))
      (node (ref "C63") (pin "2") (pinfunction "2_2") (pintype "passive"))
      (node (ref "C64") (pin "2") (pinfunction "2_2") (pintype "passive"))
      (node (ref "C65") (pin "2") (pinfunction "2_2") (pintype "passive"))
      (node (ref "C66") (pin "1") (pinfunction "1_1") (pintype "passive"))
      (node (ref "C67") (pin "1") (pinfunction "1_1") (pintype "passive"))
      (node (ref "D15") (pin "2") (pintype "passive"))
      (node (ref "D17") (pin "2") (pintype "passive"))
      (node (ref "D18") (pin "2") (pintype "passive"))
      (node (ref "D20") (pin "2") (pintype "passive"))
      (node (ref "D21") (pin "2") (pintype "passive"))
      (node (ref "J11") (pin "3") (pinfunction "GND_3") (pintype "passive"))
      (node (ref "J11") (pin "5") (pinfunction "GND_5") (pintype "passive"))
      (node (ref "J11") (pin "9") (pinfunction "GND_9") (pintype "passive"))
      (node (ref "J12") (pin "MP") (pinfunction "MP_MP") (pintype "passive"))
      (node (ref "J13") (pin "3") (pintype "passive"))
      (node (ref "J13") (pin "9") (pintype "passive"))
      (node (ref "J14") (pin "1") (pinfunction "1_1") (pintype "passive"))
      (node (ref "J14") (pin "M1") (pinfunction "MNT_M1") (pintype "passive"))
      (node (ref "J14") (pin "M2") (pinfunction "MNT_M2") (pintype "passive"))
      (node (ref "J15") (pin "1") (pinfunction "1_1") (pintype "passive"))
      (node (ref "J16") (pin "1") (pinfunction "1_1") (pintype "passive"))
      (node (ref "SWITCH_1") (pin "3") (pinfunction "3_3") (pintype "passive"))
      (node (ref "SWITCH_1") (pin "4") (pinfunction "4_4") (pintype "passive"))
      (node (ref "SWITCH_2") (pin "3") (pinfunction "3_3") (pintype "passive"))
      (node (ref "SWITCH_2") (pin "4") (pinfunction "4_4") (pintype "passive"))
      (node (ref "SWITCH_3") (pin "3") (pinfunction "3_3") (pintype "passive"))
      (node (ref "SWITCH_3") (pin "4") (pinfunction "4_4") (pintype "passive"))
      (node (ref "SWITCH_4") (pin "3") (pinfunction "3_3") (pintype "passive"))
      (node (ref "SWITCH_4") (pin "4") (pinfunction "4_4") (pintype "passive"))
      (node (ref "SWITCH_5") (pin "3") (pinfunction "3_3") (pintype "passive"))
      (node (ref "SWITCH_5") (pin "4") (pinfunction "4_4") (pintype "passive"))
      (node (ref "U16") (pin "4") (pinfunction "GND_4") (pintype "power_in"))
      (node (ref "U17") (pin "4") (pinfunction "GND_4") (pintype "power_in"))
    )
    (net (code "62") (name "NEEDLE_5V") (class "Default") (node (ref "J13") (pin "5") (pintype "passive")))
    (net (code "63") (name "Net-(J13-Pad2)") (class "Default")
      (node (ref "J13") (pin "2") (pintype "passive"))
      (node (ref "R165") (pin "1") (pinfunction "1_1") (pintype "passive"))
    )
    (net (code "64") (name "Net-(J13-Pad4)") (class "Default")
      (node (ref "J13") (pin "4") (pintype "passive"))
      (node (ref "R166") (pin "1") (pinfunction "1_1") (pintype "passive"))
    )
    (net (code "65") (name "Net-(J13-Pad10)") (class "Default")
      (node (ref "J13") (pin "10") (pintype "passive"))
      (node (ref "R164") (pin "2") (pinfunction "2_2") (pintype "passive"))
    )
    (net (code "66") (name "Net-(U16-OE)") (class "Default")
      (node (ref "R180") (pin "1") (pinfunction "1_1") (pintype "passive"))
      (node (ref "U16") (pin "5") (pinfunction "OE_5") (pintype "input"))
    )
    (net (code "67") (name "Net-(U17-VCC)") (class "Default")
      (node (ref "C66") (pin "2") (pinfunction "2_2") (pintype "passive"))
      (node (ref "C67") (pin "2") (pinfunction "2_2") (pintype "passive"))
      (node (ref "R182") (pin "2") (pinfunction "2_2") (pintype "passive"))
      (node (ref "R198") (pin "1") (pinfunction "1_1") (pintype "passive"))
      (node (ref "U17") (pin "8") (pinfunction "VCC_8") (pintype "power_in"))
    )
    (net (code "68") (name "VDD") (class "Default")
      (node (ref "J11") (pin "1") (pinfunction "VCC_1") (pintype "passive"))
    )
    (net (code "69") (name "VDDIO_Periph") (class "Default")
      (node (ref "C65") (pin "1") (pinfunction "1_1") (pintype "passive"))
      (node (ref "J13") (pin "1") (pintype "passive"))
      (node (ref "R174") (pin "2") (pinfunction "2_2") (pintype "passive"))
      (node (ref "R175") (pin "2") (pinfunction "2_2") (pintype "passive"))
      (node (ref "R180") (pin "2") (pinfunction "2_2") (pintype "passive"))
      (node (ref "R182") (pin "1") (pinfunction "1_1") (pintype "passive"))
      (node (ref "U16") (pin "1") (pinfunction "VCC(A)_1") (pintype "power_in"))
    )
    (net (code "70") (name "unconnected-(J11-KEY-Pad7)") (class "Default")
      (node (ref "J11") (pin "7") (pinfunction "KEY_7") (pintype "passive+no_connect"))
    )
    (net (code "71") (name "unconnected-(J11-TDI-Pad8)") (class "Default")
      (node (ref "J11") (pin "8") (pinfunction "TDI_8") (pintype "passive+no_connect"))
    )
    (net (code "72") (name "unconnected-(J12-Pad1)") (class "Default")
      (node (ref "J12") (pin "1") (pinfunction "1_1") (pintype "passive+no_connect"))
    )
    (net (code "73") (name "unconnected-(J12-Pad3)") (class "Default")
      (node (ref "J12") (pin "3") (pinfunction "3_3") (pintype "passive+no_connect"))
    )
    (net (code "74") (name "unconnected-(J12-Pad5)") (class "Default")
      (node (ref "J12") (pin "5") (pinfunction "5_5") (pintype "passive+no_connect"))
    )
    (net (code "75") (name "unconnected-(J13-Pad7)") (class "Default")
      (node (ref "J13") (pin "7") (pintype "passive+no_connect"))
    )
    (net (code "76") (name "unconnected-(J13-Pad8)") (class "Default")
      (node (ref "J13") (pin "8") (pintype "passive+no_connect"))
    )
  )
)
